# USB_IO_main.net
KiCad netlist of a schematic drawn in Altium Designer
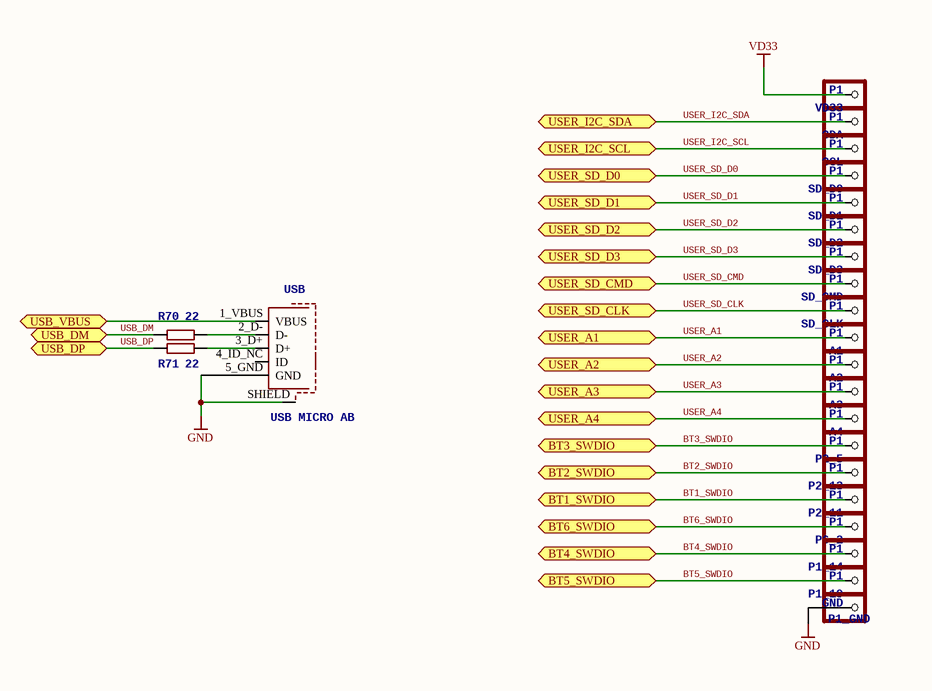
[diagram p0: USB_IO_main.SchDoc]

(export (version "E")
  (design (tool "Eeschema 10.0.6"))
  (components
    (comp (ref "A1")
      (value "P1")
      (footprint "PCB_MEDIUM_RECT_PAD")
      (description "<b>PIN HEADER</b>")
      (libsource (lib "WunderBar_v101") (part "HEADER-1X1SMD_MEDIUM"))
    )
    (comp (ref "A2")
      (value "P1")
      (footprint "PCB_MEDIUM_RECT_PAD")
      (description "<b>PIN HEADER</b>")
      (libsource (lib "WunderBar_v101") (part "HEADER-1X1SMD_MEDIUM"))
    )
    (comp (ref "A3")
      (value "P1")
      (footprint "PCB_MEDIUM_RECT_PAD")
      (description "<b>PIN HEADER</b>")
      (libsource (lib "WunderBar_v101") (part "HEADER-1X1SMD_MEDIUM"))
    )
    (comp (ref "A4")
      (value "P1")
      (footprint "PCB_MEDIUM_RECT_PAD")
      (description "<b>PIN HEADER</b>")
      (libsource (lib "WunderBar_v101") (part "HEADER-1X1SMD_MEDIUM"))
    )
    (comp (ref "P1_14")
      (value "P1")
      (footprint "PCB_MEDIUM_RECT_PAD")
      (description "<b>PIN HEADER</b>")
      (libsource (lib "WunderBar_v101") (part "HEADER-1X1SMD_MEDIUM"))
    )
    (comp (ref "P1_19")
      (value "P1")
      (footprint "PCB_MEDIUM_RECT_PAD")
      (description "<b>PIN HEADER</b>")
      (libsource (lib "WunderBar_v101") (part "HEADER-1X1SMD_MEDIUM"))
    )
    (comp (ref "P1_GND")
      (value "GND")
      (footprint "PCB_MEDIUM_RECT_PAD")
      (description "<b>PIN HEADER</b>")
      (libsource (lib "WunderBar_v101") (part "HEADER-1X1SMD_MEDIUM"))
    )
    (comp (ref "P2_5")
      (value "P1")
      (footprint "PCB_MEDIUM_RECT_PAD")
      (description "<b>PIN HEADER</b>")
      (libsource (lib "WunderBar_v101") (part "HEADER-1X1SMD_MEDIUM"))
    )
    (comp (ref "P2_11")
      (value "P1")
      (footprint "PCB_MEDIUM_RECT_PAD")
      (description "<b>PIN HEADER</b>")
      (libsource (lib "WunderBar_v101") (part "HEADER-1X1SMD_MEDIUM"))
    )
    (comp (ref "P2_13")
      (value "P1")
      (footprint "PCB_MEDIUM_RECT_PAD")
      (description "<b>PIN HEADER</b>")
      (libsource (lib "WunderBar_v101") (part "HEADER-1X1SMD_MEDIUM"))
    )
    (comp (ref "P6_2")
      (value "P1")
      (footprint "PCB_MEDIUM_RECT_PAD")
      (description "<b>PIN HEADER</b>")
      (libsource (lib "WunderBar_v101") (part "HEADER-1X1SMD_MEDIUM"))
    )
    (comp (ref "R70")
      (value "22")
      (footprint "0402")
      (description "RESISTOR")
      (libsource (lib "WunderBar_v101") (part "R-EU_0402"))
    )
    (comp (ref "R71")
      (value "22")
      (footprint "0402")
      (description "RESISTOR")
      (libsource (lib "WunderBar_v101") (part "R-EU_0402"))
    )
    (comp (ref "SCL")
      (value "P1")
      (footprint "PCB_MEDIUM_RECT_PAD")
      (description "<b>PIN HEADER</b>")
      (libsource (lib "WunderBar_v101") (part "HEADER-1X1SMD_MEDIUM"))
    )
    (comp (ref "SDA")
      (value "P1")
      (footprint "PCB_MEDIUM_RECT_PAD")
      (description "<b>PIN HEADER</b>")
      (libsource (lib "WunderBar_v101") (part "HEADER-1X1SMD_MEDIUM"))
    )
    (comp (ref "SD_CLK")
      (value "P1")
      (footprint "PCB_MEDIUM_RECT_PAD")
      (description "<b>PIN HEADER</b>")
      (libsource (lib "WunderBar_v101") (part "HEADER-1X1SMD_MEDIUM"))
    )
    (comp (ref "SD_CMD")
      (value "P1")
      (footprint "PCB_MEDIUM_RECT_PAD")
      (description "<b>PIN HEADER</b>")
      (libsource (lib "WunderBar_v101") (part "HEADER-1X1SMD_MEDIUM"))
    )
    (comp (ref "SD_D0")
      (value "P1")
      (footprint "PCB_MEDIUM_RECT_PAD")
      (description "<b>PIN HEADER</b>")
      (libsource (lib "WunderBar_v101") (part "HEADER-1X1SMD_MEDIUM"))
    )
    (comp (ref "SD_D1")
      (value "P1")
      (footprint "PCB_MEDIUM_RECT_PAD")
      (description "<b>PIN HEADER</b>")
      (libsource (lib "WunderBar_v101") (part "HEADER-1X1SMD_MEDIUM"))
    )
    (comp (ref "SD_D2")
      (value "P1")
      (footprint "PCB_MEDIUM_RECT_PAD")
      (description "<b>PIN HEADER</b>")
      (libsource (lib "WunderBar_v101") (part "HEADER-1X1SMD_MEDIUM"))
    )
    (comp (ref "SD_D3")
      (value "P1")
      (footprint "PCB_MEDIUM_RECT_PAD")
      (description "<b>PIN HEADER</b>")
      (libsource (lib "WunderBar_v101") (part "HEADER-1X1SMD_MEDIUM"))
    )
    (comp (ref "USB")
      (value "USB MICRO AB")
      (footprint "USB_MICRO_SMD")
      (description "Micro USB right angle (AB) connector")
      (libsource (lib "WunderBar_v101") (part "USB_MICROSMD"))
    )
    (comp (ref "VD33")
      (value "P1")
      (footprint "PCB_MEDIUM_RECT_PAD")
      (description "<b>PIN HEADER</b>")
      (libsource (lib "WunderBar_v101") (part "HEADER-1X1SMD_MEDIUM"))
    )
  )
  (nets
    (net (code "1") (name "/BT1_SWDIO") (class "Default")
      (node (ref "P2_11") (pin "1") (pinfunction "1_1") (pintype "passive"))
    )
    (net (code "2") (name "/BT2_SWDIO") (class "Default")
      (node (ref "P2_13") (pin "1") (pinfunction "1_1") (pintype "passive"))
    )
    (net (code "3") (name "/BT3_SWDIO") (class "Default")
      (node (ref "P2_5") (pin "1") (pinfunction "1_1") (pintype "passive"))
    )
    (net (code "4") (name "/BT4_SWDIO") (class "Default")
      (node (ref "P1_14") (pin "1") (pinfunction "1_1") (pintype "passive"))
    )
    (net (code "5") (name "/BT5_SWDIO") (class "Default")
      (node (ref "P1_19") (pin "1") (pinfunction "1_1") (pintype "passive"))
    )
    (net (code "6") (name "/BT6_SWDIO") (class "Default")
      (node (ref "P6_2") (pin "1") (pinfunction "1_1") (pintype "passive"))
    )
    (net (code "7") (name "/USB_DM") (class "Default")
      (node (ref "R70") (pin "2") (pinfunction "2_2") (pintype "passive"))
    )
    (net (code "8") (name "/USB_DP") (class "Default")
      (node (ref "R71") (pin "2") (pinfunction "2_2") (pintype "passive"))
    )
    (net (code "9") (name "/USB_VBUS") (class "Default")
      (node (ref "USB") (pin "1_VBUS") (pinfunction "VBUS_1_VBUS") (pintype "power_in"))
    )
    (net (code "10") (name "/USER_A1") (class "Default")
      (node (ref "A1") (pin "1") (pinfunction "1_1") (pintype "passive"))
    )
    (net (code "11") (name "/USER_A2") (class "Default")
      (node (ref "A2") (pin "1") (pinfunction "1_1") (pintype "passive"))
    )
    (net (code "12") (name "/USER_A3") (class "Default")
      (node (ref "A3") (pin "1") (pinfunction "1_1") (pintype "passive"))
    )
    (net (code "13") (name "/USER_A4") (class "Default")
      (node (ref "A4") (pin "1") (pinfunction "1_1") (pintype "passive"))
    )
    (net (code "14") (name "/USER_I2C_SCL") (class "Default")
      (node (ref "SCL") (pin "1") (pinfunction "1_1") (pintype "passive"))
    )
    (net (code "15") (name "/USER_I2C_SDA") (class "Default")
      (node (ref "SDA") (pin "1") (pinfunction "1_1") (pintype "passive"))
    )
    (net (code "16") (name "/USER_SD_CLK") (class "Default")
      (node (ref "SD_CLK") (pin "1") (pinfunction "1_1") (pintype "passive"))
    )
    (net (code "17") (name "/USER_SD_CMD") (class "Default")
      (node (ref "SD_CMD") (pin "1") (pinfunction "1_1") (pintype "passive"))
    )
    (net (code "18") (name "/USER_SD_D0") (class "Default")
      (node (ref "SD_D0") (pin "1") (pinfunction "1_1") (pintype "passive"))
    )
    (net (code "19") (name "/USER_SD_D1") (class "Default")
      (node (ref "SD_D1") (pin "1") (pinfunction "1_1") (pintype "passive"))
    )
    (net (code "20") (name "/USER_SD_D2") (class "Default")
      (node (ref "SD_D2") (pin "1") (pinfunction "1_1") (pintype "passive"))
    )
    (net (code "21") (name "/USER_SD_D3") (class "Default")
      (node (ref "SD_D3") (pin "1") (pinfunction "1_1") (pintype "passive"))
    )
    (net (code "22") (name "GND") (class "Default")
      (node (ref "P1_GND") (pin "1") (pinfunction "1_1") (pintype "passive"))
      (node (ref "USB") (pin "5_GND") (pinfunction "GND_5_GND") (pintype "power_in"))
      (node (ref "USB") (pin "SHIELD") (pinfunction "SHIELD_SHIELD") (pintype "passive"))
    )
    (net (code "23") (name "Net-(USB-D+)") (class "Default")
      (node (ref "R71") (pin "1") (pinfunction "1_1") (pintype "passive"))
      (node (ref "USB") (pin "3_D+") (pinfunction "D+_3_D+") (pintype "passive"))
    )
    (net (code "24") (name "Net-(USB-D-)") (class "Default")
      (node (ref "R70") (pin "1") (pinfunction "1_1") (pintype "passive"))
      (node (ref "USB") (pin "2_D-") (pinfunction "D-_2_D-") (pintype "passive"))
    )
    (net (code "25") (name "VD33") (class "Default")
      (node (ref "VD33") (pin "1") (pinfunction "1_1") (pintype "passive"))
    )
    (net (code "26") (name "unconnected-(USB-ID-Pad4_ID_NC)") (class "Default")
      (node (ref "USB") (pin "4_ID_NC") (pinfunction "ID_4_ID_NC") (pintype "passive"))
    )
  )
)
